# 9_USB.net
KiCad netlist of a schematic drawn in Altium Designer
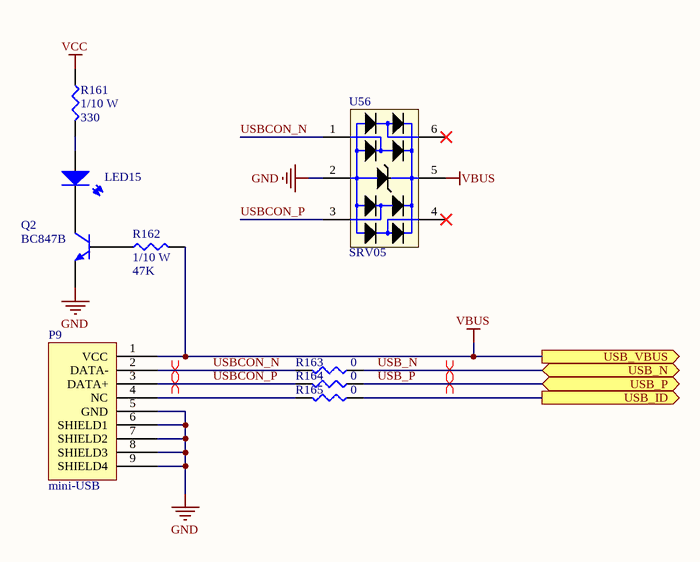
[diagram p0: [9] USB.SchDoc]

(export (version "E")
  (design (tool "Eeschema 10.0.6"))
  (components
    (comp (ref "LED15") (value "LED 0603") (footprint "LED 0603") (libsource (lib "LEDs") (part "LED0603")))
    (comp (ref "P9")
      (value "mini-USB")
      (footprint "USB/SM0.8-6H5")
      (libsource (lib "Connectors") (part "miniUSB"))
    )
    (comp (ref "Q2")
      (value "BC847B")
      (footprint "SOT23")
      (description "SOT23 NPN Silicon Planar General Purpose Transistor")
      (fields (field (name "PUBLISHER") "Altium Limited"))
      (libsource (lib "Zetex Discrete BJT") (part "BC847B"))
    )
    (comp (ref "R161")
      (value "330")
      (footprint "RES0805")
      (description "Think Film Chip resistor")
      (fields
        (field (name "TOLERANCE") "1%")
        (field (name "RATING") "1/10 W")
        (field (name "Comment") "ChipRes 330R 1%")
      )
      (libsource (lib "Resistors") (part "ChipRes 330R 1%"))
    )
    (comp (ref "R162")
      (value "47K")
      (footprint "RES0805")
      (description "Think Film Chip resistor")
      (fields
        (field (name "TOLERANCE") "1%")
        (field (name "RATING") "1/10 W")
        (field (name "Comment") "ChipRes 47K 1%")
      )
      (libsource (lib "Resistors") (part "ChipRes 47K 1%"))
    )
    (comp (ref "R163")
      (value "0")
      (footprint "RES0805")
      (description "Chip resistor")
      (fields (field (name "Comment") "ChipRes"))
      (libsource (lib "Common Devices") (part "ChipRes"))
    )
    (comp (ref "R164")
      (value "0")
      (footprint "RES0805")
      (description "Chip resistor")
      (fields (field (name "Comment") "ChipRes"))
      (libsource (lib "Common Devices") (part "ChipRes"))
    )
    (comp (ref "R165")
      (value "0")
      (footprint "RES0805")
      (description "Chip resistor")
      (fields (field (name "Comment") "ChipRes"))
      (libsource (lib "Common Devices") (part "ChipRes"))
    )
    (comp (ref "U56")
      (value "SRV05")
      (footprint "SOT23-6")
      (description "Protection 6V 10A")
      (libsource (lib "Protection") (part "SRV05"))
    )
  )
  (nets
    (net (code "1") (name "/USBCON_N") (class "Default")
      (node (ref "P9") (pin "2") (pinfunction "DATA-_2") (pintype "passive"))
      (node (ref "R163") (pin "2") (pintype "passive"))
      (node (ref "U56") (pin "1") (pinfunction "1_1") (pintype "passive"))
    )
    (net (code "2") (name "/USBCON_P") (class "Default")
      (node (ref "P9") (pin "3") (pinfunction "DATA+_3") (pintype "passive"))
      (node (ref "R164") (pin "2") (pintype "passive"))
      (node (ref "U56") (pin "3") (pinfunction "3_3") (pintype "passive"))
    )
    (net (code "3") (name "/USB_ID") (class "Default") (node (ref "R165") (pin "1") (pintype "passive")))
    (net (code "4") (name "/USB_N") (class "Default") (node (ref "R163") (pin "1") (pintype "passive")))
    (net (code "5") (name "/USB_P") (class "Default") (node (ref "R164") (pin "1") (pintype "passive")))
    (net (code "6") (name "GND") (class "Default")
      (node (ref "P9") (pin "5") (pinfunction "GND_5") (pintype "passive"))
      (node (ref "P9") (pin "6") (pinfunction "SHIELD1_6") (pintype "passive"))
      (node (ref "P9") (pin "7") (pinfunction "SHIELD2_7") (pintype "passive"))
      (node (ref "P9") (pin "8") (pinfunction "SHIELD3_8") (pintype "passive"))
      (node (ref "P9") (pin "9") (pinfunction "SHIELD4_9") (pintype "passive"))
      (node (ref "Q2") (pin "2") (pinfunction "E_2") (pintype "passive"))
      (node (ref "U56") (pin "2") (pinfunction "2_2") (pintype "passive"))
    )
    (net (code "7") (name "Net-(LED15-Pad2)") (class "Default")
      (node (ref "LED15") (pin "2") (pinfunction "2_2") (pintype "passive"))
      (node (ref "R161") (pin "2") (pintype "passive"))
    )
    (net (code "8") (name "Net-(P9-NC)") (class "Default")
      (node (ref "P9") (pin "4") (pinfunction "NC_4") (pintype "passive"))
      (node (ref "R165") (pin "2") (pintype "passive"))
    )
    (net (code "9") (name "Net-(Q2-B)") (class "Default")
      (node (ref "Q2") (pin "3") (pinfunction "B_3") (pintype "passive"))
      (node (ref "R162") (pin "1") (pintype "passive"))
    )
    (net (code "10") (name "Net-(Q2-C)") (class "Default")
      (node (ref "LED15") (pin "1") (pinfunction "1_1") (pintype "passive"))
      (node (ref "Q2") (pin "1") (pinfunction "C_1") (pintype "passive"))
    )
    (net (code "11") (name "VBUS") (class "Default")
      (node (ref "P9") (pin "1") (pinfunction "VCC_1") (pintype "passive"))
      (node (ref "R162") (pin "2") (pintype "passive"))
      (node (ref "U56") (pin "5") (pinfunction "5_5") (pintype "passive"))
    )
    (net (code "12") (name "VCC") (class "Default") (node (ref "R161") (pin "1") (pintype "passive")))
    (net (code "13") (name "unconnected-(U56-Pad4)") (class "Default")
      (node (ref "U56") (pin "4") (pinfunction "4_4") (pintype "passive+no_connect"))
    )
    (net (code "14") (name "unconnected-(U56-Pad6)") (class "Default")
      (node (ref "U56") (pin "6") (pinfunction "6_6") (pintype "passive+no_connect"))
    )
  )
)
